# Power_Over_Ethernet.net
KiCad netlist of a schematic drawn in Altium Designer
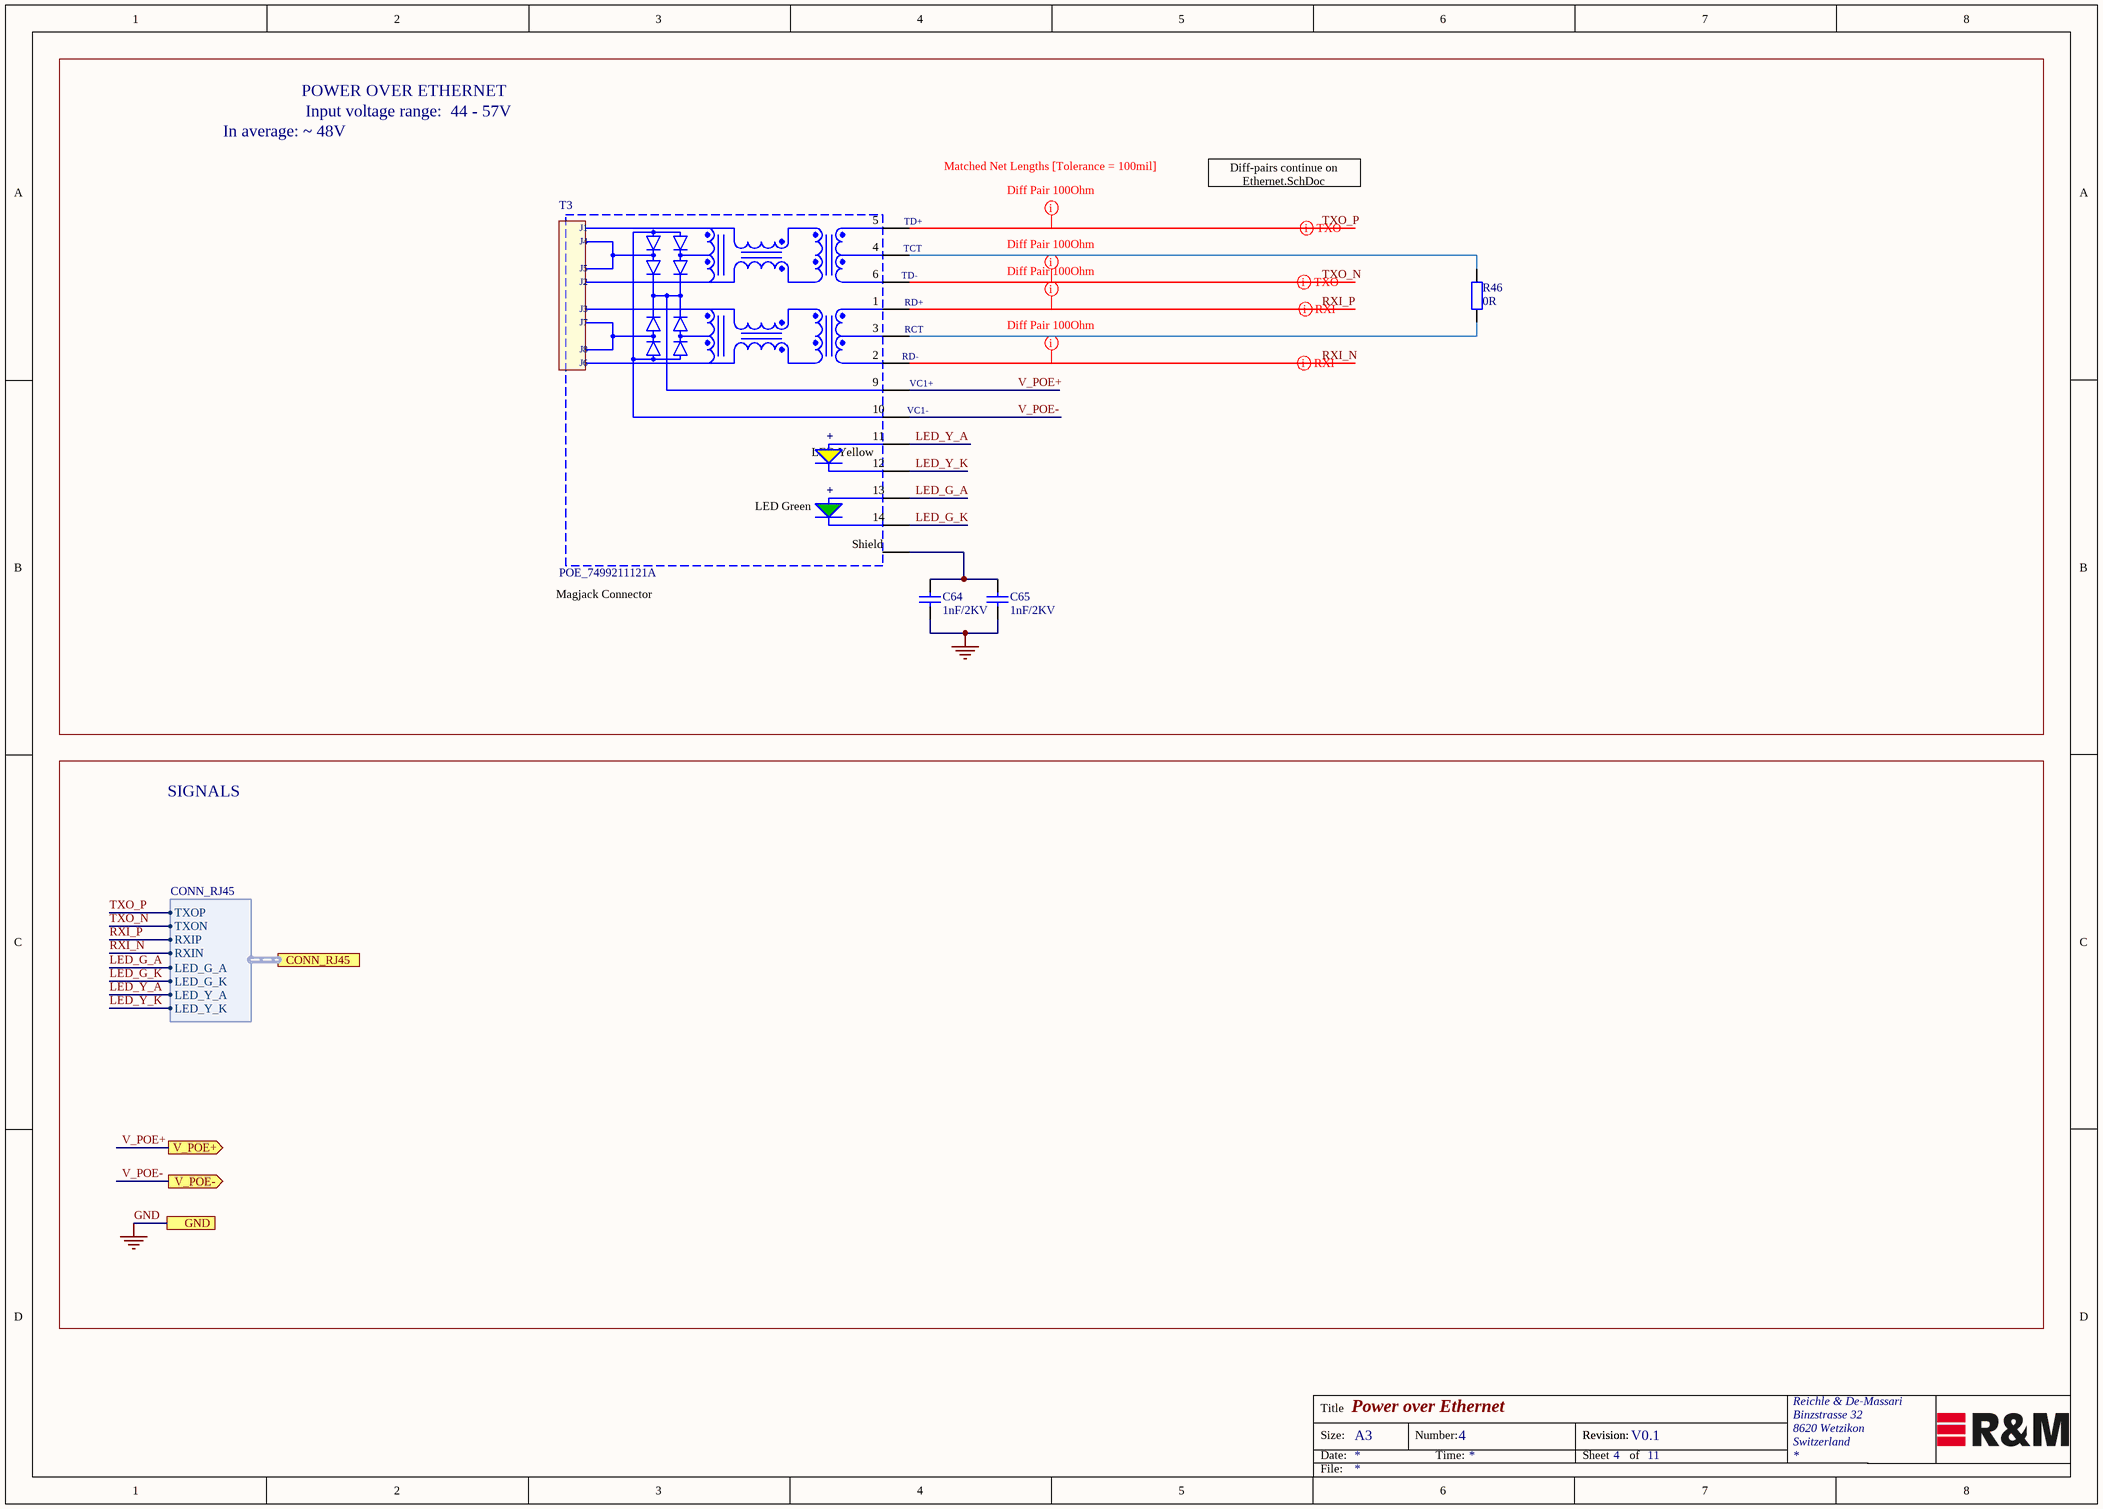
[diagram p0: Power_Over_Ethernet.SchDoc]

(export (version "E")
  (design (tool "Eeschema 10.0.6"))
  (components
    (comp (ref "C64")
      (value "1nF/2KV")
      (footprint "Ceramic Capacitor 1206 EIA")
      (description "1000pF ±10% 2000V (2kV) Ceramic Capacitor X7R 1206 (3216 Metric)")
      (fields (field (name "TOLERANCE") "±10%") (field (name "VOLTAGE") "2kV"))
      (libsource (lib "RDM_ALT_SCH") (part "Cap_1nF_1206_2000V"))
    )
    (comp (ref "C65")
      (value "1nF/2KV")
      (footprint "Ceramic Capacitor 1206 EIA")
      (description "1000pF ±10% 2000V (2kV) Ceramic Capacitor X7R 1206 (3216 Metric)")
      (fields (field (name "TOLERANCE") "±10%") (field (name "VOLTAGE") "2kV"))
      (libsource (lib "RDM_ALT_SCH") (part "Cap_1nF_1206_2000V"))
    )
    (comp (ref "R46")
      (value "0R")
      (footprint "Resistor 0805 EIA")
      (description "0 Ohms Jumper 0.125W, 1/8W Chip Resistor 0805 (2012 Metric) Automotive AEC-Q200 Thick Film")
      (fields
        (field (name "POWER") "0.125W, 1/8W")
        (field (name "MANUFACTURER") "Panasonic Electronic Components")
      )
      (libsource (lib "RDM_ALT_SCH") (part "Res_0R_0805"))
    )
    (comp (ref "T3")
      (value "POE_7499211121A")
      (footprint "PoE_7499211121A")
      (fields (field (name "POWER") "PoE (up to 350 mA)") (field (name "TOLERANCE") "NA"))
      (libsource (lib "RDM_ALT_SCH") (part "CONN_RJ45_PoE"))
    )
  )
  (nets
    (net (code "2") (name "/LED_G_A") (class "Default")
      (node (ref "T3") (pin "13") (pinfunction "13_13") (pintype "passive"))
    )
    (net (code "3") (name "/LED_G_K") (class "Default")
      (node (ref "T3") (pin "14") (pinfunction "14_14") (pintype "passive"))
    )
    (net (code "4") (name "/LED_Y_A") (class "Default")
      (node (ref "T3") (pin "11") (pinfunction "11_11") (pintype "passive"))
    )
    (net (code "5") (name "/LED_Y_K") (class "Default")
      (node (ref "T3") (pin "12") (pinfunction "12_12") (pintype "passive"))
    )
    (net (code "6") (name "/RXI_N") (class "Default")
      (node (ref "T3") (pin "2") (pinfunction "RD-_2") (pintype "passive"))
    )
    (net (code "7") (name "/RXI_P") (class "Default")
      (node (ref "T3") (pin "1") (pinfunction "RD+_1") (pintype "passive"))
    )
    (net (code "8") (name "/TXO_N") (class "Default")
      (node (ref "T3") (pin "6") (pinfunction "TD-_6") (pintype "passive"))
    )
    (net (code "9") (name "/TXO_P") (class "Default")
      (node (ref "T3") (pin "5") (pinfunction "TD+_5") (pintype "passive"))
    )
    (net (code "10") (name "/V_POE+") (class "Default")
      (node (ref "T3") (pin "9") (pinfunction "VC1+_9") (pintype "passive"))
    )
    (net (code "11") (name "/V_POE-") (class "Default")
      (node (ref "T3") (pin "10") (pinfunction "VC1-_10") (pintype "passive"))
    )
    (net (code "13") (name "GND") (class "Default")
      (node (ref "C64") (pin "1") (pinfunction "1_1") (pintype "passive"))
      (node (ref "C65") (pin "1") (pinfunction "1_1") (pintype "passive"))
    )
    (net (code "14") (name "Net-(C64-Pad2)") (class "Default")
      (node (ref "C64") (pin "2") (pinfunction "2_2") (pintype "passive"))
      (node (ref "C65") (pin "2") (pinfunction "2_2") (pintype "passive"))
      (node (ref "T3") (pin "Shield") (pinfunction "Shield_Shield") (pintype "passive"))
    )
    (net (code "15") (name "Net-(T3-RCT)") (class "Default")
      (node (ref "R46") (pin "2") (pinfunction "2_2") (pintype "passive"))
      (node (ref "T3") (pin "3") (pinfunction "RCT_3") (pintype "passive"))
    )
    (net (code "16") (name "Net-(T3-TCT)") (class "Default")
      (node (ref "R46") (pin "1") (pinfunction "1_1") (pintype "passive"))
      (node (ref "T3") (pin "4") (pinfunction "TCT_4") (pintype "passive"))
    )
  )
)
